# hv_io_gpio.net
KiCad netlist of a schematic drawn in Altium Designer
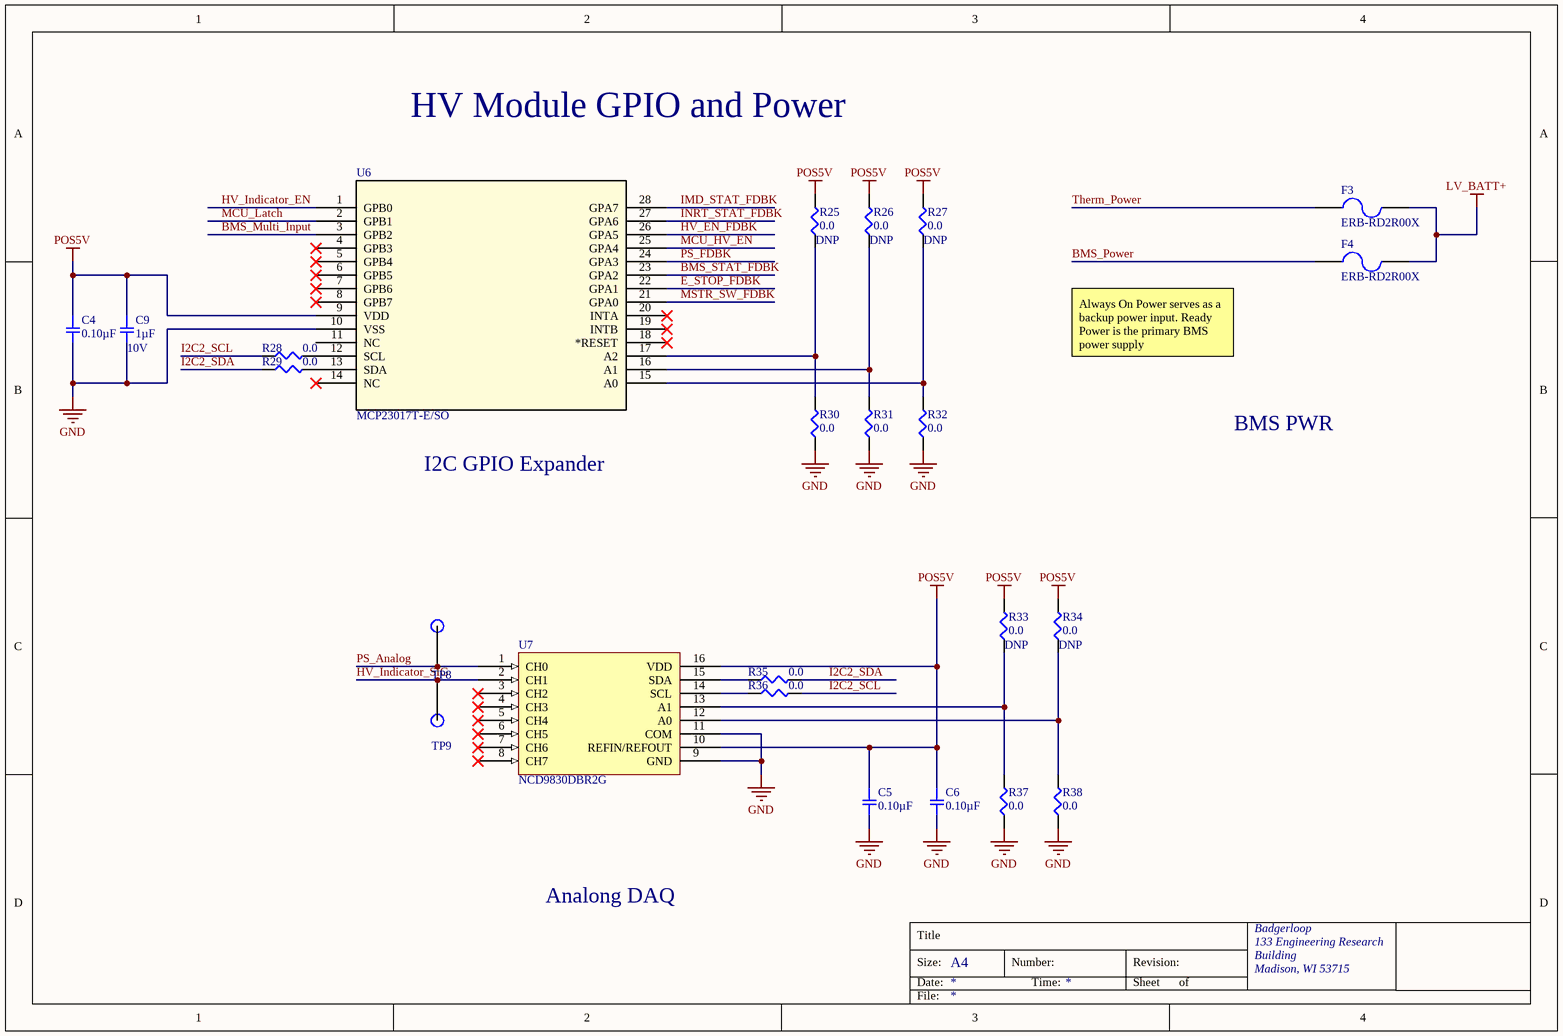
[diagram p0: hv_io_gpio.SchDoc]

(export (version "E")
  (design (tool "Eeschema 10.0.6"))
  (components
    (comp (ref "C4")
      (value "0.10µF")
      (footprint "SMD-0805C")
      (description "CAP CER 0.1UF 50V X7R 0805")
      (fields
        (field (name "DIGI-KEY PART NUMBER") "490-5803-1-ND")
        (field (name "PART NUMBER") "GCJ21BR71H104KA01L")
      )
      (libsource (lib "capacitor") (part "GCJ21BR71H104KA01L"))
    )
    (comp (ref "C5")
      (value "0.10µF")
      (footprint "SMD-0805C")
      (description "CAP CER 0.1UF 50V X7R 0805")
      (fields
        (field (name "DIGI-KEY PART NUMBER") "490-5803-1-ND")
        (field (name "PART NUMBER") "GCJ21BR71H104KA01L")
      )
      (libsource (lib "capacitor") (part "GCJ21BR71H104KA01L"))
    )
    (comp (ref "C6")
      (value "0.10µF")
      (footprint "SMD-0805C")
      (description "CAP CER 0.1UF 50V X7R 0805")
      (fields
        (field (name "DIGI-KEY PART NUMBER") "490-5803-1-ND")
        (field (name "PART NUMBER") "GCJ21BR71H104KA01L")
      )
      (libsource (lib "capacitor") (part "GCJ21BR71H104KA01L"))
    )
    (comp (ref "C9")
      (value "1µF")
      (footprint "SMD-0402C")
      (description "CAP CER 1UF 10V X7S 0402")
      (fields
        (field (name "PART NUMBER") "GCM155C71A105KE38D")
        (field (name "MANUFACTURER") "Murata Electronics North America")
        (field (name "VOLTAGE") "10V")
      )
      (libsource (lib "altium-import") (part "root_0_GCM155C71A105KE38D_"))
    )
    (comp (ref "F3")
      (value "ERB-RD2R00X")
      (footprint "SMD-0402-RES")
      (description "FUSE BOARD MOUNT 2A 32VDC 0402")
      (fields (field (name "MANUFACTURER") "Panasonic"))
      (libsource (lib "temp") (part "ERB-RD2R00X"))
    )
    (comp (ref "F4")
      (value "ERB-RD2R00X")
      (footprint "SMD-0402-RES")
      (description "FUSE BOARD MOUNT 2A 32VDC 0402")
      (fields (field (name "MANUFACTURER") "Panasonic"))
      (libsource (lib "temp") (part "ERB-RD2R00X"))
    )
    (comp (ref "R25")
      (value "0.0")
      (footprint "SMD-0402-RES")
      (description "RES SMD 0.0OHM JUMPER 1/10W 0402")
      (fields
        (field (name "PART NUMBER") "ERJ-2GE0R00X")
        (field (name "DIGI-KEY PART NUMBER") "P0.0JCT-ND")
        (field (name "DNP") "DNP")
      )
      (libsource (lib "altium-import") (part "root_1_ERJ-2GE0R00X_"))
    )
    (comp (ref "R26")
      (value "0.0")
      (footprint "SMD-0402-RES")
      (description "RES SMD 0.0OHM JUMPER 1/10W 0402")
      (fields
        (field (name "PART NUMBER") "ERJ-2GE0R00X")
        (field (name "DIGI-KEY PART NUMBER") "P0.0JCT-ND")
        (field (name "DNP") "DNP")
      )
      (libsource (lib "altium-import") (part "root_1_ERJ-2GE0R00X_"))
    )
    (comp (ref "R27")
      (value "0.0")
      (footprint "SMD-0402-RES")
      (description "RES SMD 0.0OHM JUMPER 1/10W 0402")
      (fields
        (field (name "PART NUMBER") "ERJ-2GE0R00X")
        (field (name "DIGI-KEY PART NUMBER") "P0.0JCT-ND")
        (field (name "DNP") "DNP")
      )
      (libsource (lib "altium-import") (part "root_1_ERJ-2GE0R00X_"))
    )
    (comp (ref "R28")
      (value "0.0")
      (footprint "SMD-0402-RES")
      (description "RES SMD 0.0OHM JUMPER 1/10W 0402")
      (fields (field (name "PART NUMBER") "ERJ-2GE0R00X") (field (name "DIGI-KEY PART NUMBER") "P0.0JCT-ND"))
      (libsource (lib "altium-import") (part "root_0_ERJ-2GE0R00X_"))
    )
    (comp (ref "R29")
      (value "0.0")
      (footprint "SMD-0402-RES")
      (description "RES SMD 0.0OHM JUMPER 1/10W 0402")
      (fields (field (name "PART NUMBER") "ERJ-2GE0R00X") (field (name "DIGI-KEY PART NUMBER") "P0.0JCT-ND"))
      (libsource (lib "altium-import") (part "root_0_ERJ-2GE0R00X_"))
    )
    (comp (ref "R30")
      (value "0.0")
      (footprint "SMD-0402-RES")
      (description "RES SMD 0.0OHM JUMPER 1/10W 0402")
      (fields (field (name "PART NUMBER") "ERJ-2GE0R00X") (field (name "DIGI-KEY PART NUMBER") "P0.0JCT-ND"))
      (libsource (lib "altium-import") (part "root_1_ERJ-2GE0R00X_"))
    )
    (comp (ref "R31")
      (value "0.0")
      (footprint "SMD-0402-RES")
      (description "RES SMD 0.0OHM JUMPER 1/10W 0402")
      (fields (field (name "PART NUMBER") "ERJ-2GE0R00X") (field (name "DIGI-KEY PART NUMBER") "P0.0JCT-ND"))
      (libsource (lib "altium-import") (part "root_1_ERJ-2GE0R00X_"))
    )
    (comp (ref "R32")
      (value "0.0")
      (footprint "SMD-0402-RES")
      (description "RES SMD 0.0OHM JUMPER 1/10W 0402")
      (fields (field (name "PART NUMBER") "ERJ-2GE0R00X") (field (name "DIGI-KEY PART NUMBER") "P0.0JCT-ND"))
      (libsource (lib "altium-import") (part "root_1_ERJ-2GE0R00X_"))
    )
    (comp (ref "R33")
      (value "0.0")
      (footprint "SMD-0402-RES")
      (description "RES SMD 0.0OHM JUMPER 1/10W 0402")
      (fields
        (field (name "PART NUMBER") "ERJ-2GE0R00X")
        (field (name "DIGI-KEY PART NUMBER") "P0.0JCT-ND")
        (field (name "DNP") "DNP")
      )
      (libsource (lib "altium-import") (part "root_1_ERJ-2GE0R00X_"))
    )
    (comp (ref "R34")
      (value "0.0")
      (footprint "SMD-0402-RES")
      (description "RES SMD 0.0OHM JUMPER 1/10W 0402")
      (fields
        (field (name "PART NUMBER") "ERJ-2GE0R00X")
        (field (name "DIGI-KEY PART NUMBER") "P0.0JCT-ND")
        (field (name "DNP") "DNP")
      )
      (libsource (lib "altium-import") (part "root_1_ERJ-2GE0R00X_"))
    )
    (comp (ref "R35")
      (value "0.0")
      (footprint "SMD-0402-RES")
      (description "RES SMD 0.0OHM JUMPER 1/10W 0402")
      (fields (field (name "PART NUMBER") "ERJ-2GE0R00X") (field (name "DIGI-KEY PART NUMBER") "P0.0JCT-ND"))
      (libsource (lib "altium-import") (part "root_0_ERJ-2GE0R00X_"))
    )
    (comp (ref "R36")
      (value "0.0")
      (footprint "SMD-0402-RES")
      (description "RES SMD 0.0OHM JUMPER 1/10W 0402")
      (fields (field (name "PART NUMBER") "ERJ-2GE0R00X") (field (name "DIGI-KEY PART NUMBER") "P0.0JCT-ND"))
      (libsource (lib "altium-import") (part "root_0_ERJ-2GE0R00X_"))
    )
    (comp (ref "R37")
      (value "0.0")
      (footprint "SMD-0402-RES")
      (description "RES SMD 0.0OHM JUMPER 1/10W 0402")
      (fields (field (name "PART NUMBER") "ERJ-2GE0R00X") (field (name "DIGI-KEY PART NUMBER") "P0.0JCT-ND"))
      (libsource (lib "altium-import") (part "root_1_ERJ-2GE0R00X_"))
    )
    (comp (ref "R38")
      (value "0.0")
      (footprint "SMD-0402-RES")
      (description "RES SMD 0.0OHM JUMPER 1/10W 0402")
      (fields (field (name "PART NUMBER") "ERJ-2GE0R00X") (field (name "DIGI-KEY PART NUMBER") "P0.0JCT-ND"))
      (libsource (lib "altium-import") (part "root_1_ERJ-2GE0R00X_"))
    )
    (comp (ref "TP8") (value "TP") (footprint "Test Point") (libsource (lib "misc") (part "TP")))
    (comp (ref "TP9") (value "TP") (footprint "Test Point") (libsource (lib "misc") (part "TP")))
    (comp (ref "U6")
      (value "MCP23017T-E/SO")
      (footprint "SOIC28-W_MC-M")
      (description "IC I/O EXPANDER I2C 16B 28SOIC")
      (fields (field (name "MANUFACTURER") "Microchip"))
      (libsource (lib "ic") (part "MCP23017T-E/SO"))
    )
    (comp (ref "U7")
      (value "NCD9830DBR2G")
      (footprint "TSOP65P640X120_HS-17N")
      (description "IC ADC 8BIT 8CH I2C 16TSSOP")
      (fields (field (name "MANUFACTURER") "ON Semiconductor"))
      (libsource (lib "ic") (part "NCD9830DBR2G"))
    )
  )
  (nets
    (net (code "1") (name "/BMS_Multi_Input") (class "Default")
      (node (ref "U6") (pin "3") (pinfunction "GPB2_3") (pintype "passive"))
    )
    (net (code "2") (name "/BMS_Power") (class "Default")
      (node (ref "F4") (pin "1") (pinfunction "1_1") (pintype "passive"))
    )
    (net (code "3") (name "/BMS_STAT_FDBK") (class "Default")
      (node (ref "U6") (pin "23") (pinfunction "GPA2_23") (pintype "passive"))
    )
    (net (code "4") (name "/E_STOP_FDBK") (class "Default")
      (node (ref "U6") (pin "22") (pinfunction "GPA1_22") (pintype "passive"))
    )
    (net (code "5") (name "/HV_EN_FDBK") (class "Default")
      (node (ref "U6") (pin "26") (pinfunction "GPA5_26") (pintype "passive"))
    )
    (net (code "6") (name "/HV_Indicator_EN") (class "Default")
      (node (ref "U6") (pin "1") (pinfunction "GPB0_1") (pintype "passive"))
    )
    (net (code "7") (name "/HV_Indicator_SIG") (class "Default")
      (node (ref "TP9") (pin "1") (pinfunction "1_1") (pintype "passive"))
      (node (ref "U7") (pin "2") (pinfunction "CH1_2") (pintype "input"))
    )
    (net (code "8") (name "/I2C2_SCL") (class "Default")
      (node (ref "R28") (pin "1") (pinfunction "1_1") (pintype "passive"))
      (node (ref "R36") (pin "2") (pinfunction "2_2") (pintype "passive"))
    )
    (net (code "9") (name "/I2C2_SDA") (class "Default")
      (node (ref "R29") (pin "1") (pinfunction "1_1") (pintype "passive"))
      (node (ref "R35") (pin "2") (pinfunction "2_2") (pintype "passive"))
    )
    (net (code "10") (name "/IMD_STAT_FDBK") (class "Default")
      (node (ref "U6") (pin "28") (pinfunction "GPA7_28") (pintype "passive"))
    )
    (net (code "11") (name "/INRT_STAT_FDBK") (class "Default")
      (node (ref "U6") (pin "27") (pinfunction "GPA6_27") (pintype "passive"))
    )
    (net (code "12") (name "/MCU_HV_EN") (class "Default")
      (node (ref "U6") (pin "25") (pinfunction "GPA4_25") (pintype "passive"))
    )
    (net (code "13") (name "/MCU_Latch") (class "Default")
      (node (ref "U6") (pin "2") (pinfunction "GPB1_2") (pintype "passive"))
    )
    (net (code "14") (name "/MSTR_SW_FDBK") (class "Default")
      (node (ref "U6") (pin "21") (pinfunction "GPA0_21") (pintype "passive"))
    )
    (net (code "15") (name "/PS_Analog") (class "Default")
      (node (ref "TP8") (pin "1") (pinfunction "1_1") (pintype "passive"))
      (node (ref "U7") (pin "1") (pinfunction "CH0_1") (pintype "input"))
    )
    (net (code "16") (name "/PS_FDBK") (class "Default")
      (node (ref "U6") (pin "24") (pinfunction "GPA3_24") (pintype "passive"))
    )
    (net (code "17") (name "/Therm_Power") (class "Default")
      (node (ref "F3") (pin "1") (pinfunction "1_1") (pintype "passive"))
    )
    (net (code "18") (name "GND") (class "Default")
      (node (ref "C4") (pin "2") (pinfunction "2_2") (pintype "passive"))
      (node (ref "C5") (pin "2") (pinfunction "2_2") (pintype "passive"))
      (node (ref "C6") (pin "2") (pinfunction "2_2") (pintype "passive"))
      (node (ref "C9") (pin "2") (pinfunction "2_2") (pintype "passive"))
      (node (ref "R30") (pin "1") (pinfunction "1_1") (pintype "passive"))
      (node (ref "R31") (pin "1") (pinfunction "1_1") (pintype "passive"))
      (node (ref "R32") (pin "1") (pinfunction "1_1") (pintype "passive"))
      (node (ref "R37") (pin "1") (pinfunction "1_1") (pintype "passive"))
      (node (ref "R38") (pin "1") (pinfunction "1_1") (pintype "passive"))
      (node (ref "U6") (pin "10") (pinfunction "VSS_10") (pintype "passive"))
      (node (ref "U7") (pin "11") (pinfunction "COM_11") (pintype "power_in"))
      (node (ref "U7") (pin "9") (pinfunction "GND_9") (pintype "power_in"))
    )
    (net (code "19") (name "LV_BATT+") (class "Default")
      (node (ref "F3") (pin "2") (pinfunction "2_2") (pintype "passive"))
      (node (ref "F4") (pin "2") (pinfunction "2_2") (pintype "passive"))
    )
    (net (code "20") (name "Net-(U6-A0)") (class "Default")
      (node (ref "R27") (pin "1") (pinfunction "1_1") (pintype "passive"))
      (node (ref "R32") (pin "2") (pinfunction "2_2") (pintype "passive"))
      (node (ref "U6") (pin "15") (pinfunction "A0_15") (pintype "passive"))
    )
    (net (code "21") (name "Net-(U6-A1)") (class "Default")
      (node (ref "R26") (pin "1") (pinfunction "1_1") (pintype "passive"))
      (node (ref "R31") (pin "2") (pinfunction "2_2") (pintype "passive"))
      (node (ref "U6") (pin "16") (pinfunction "A1_16") (pintype "passive"))
    )
    (net (code "22") (name "Net-(U6-A2)") (class "Default")
      (node (ref "R25") (pin "1") (pinfunction "1_1") (pintype "passive"))
      (node (ref "R30") (pin "2") (pinfunction "2_2") (pintype "passive"))
      (node (ref "U6") (pin "17") (pinfunction "A2_17") (pintype "passive"))
    )
    (net (code "23") (name "Net-(U6-SCL)") (class "Default")
      (node (ref "R28") (pin "2") (pinfunction "2_2") (pintype "passive"))
      (node (ref "U6") (pin "12") (pinfunction "SCL_12") (pintype "passive"))
    )
    (net (code "24") (name "Net-(U6-SDA)") (class "Default")
      (node (ref "R29") (pin "2") (pinfunction "2_2") (pintype "passive"))
      (node (ref "U6") (pin "13") (pinfunction "SDA_13") (pintype "passive"))
    )
    (net (code "25") (name "Net-(U7-A0)") (class "Default")
      (node (ref "R34") (pin "1") (pinfunction "1_1") (pintype "passive"))
      (node (ref "R38") (pin "2") (pinfunction "2_2") (pintype "passive"))
      (node (ref "U7") (pin "12") (pinfunction "A0_12") (pintype "passive"))
    )
    (net (code "26") (name "Net-(U7-A1)") (class "Default")
      (node (ref "R33") (pin "1") (pinfunction "1_1") (pintype "passive"))
      (node (ref "R37") (pin "2") (pinfunction "2_2") (pintype "passive"))
      (node (ref "U7") (pin "13") (pinfunction "A1_13") (pintype "passive"))
    )
    (net (code "27") (name "Net-(U7-SCL)") (class "Default")
      (node (ref "R36") (pin "1") (pinfunction "1_1") (pintype "passive"))
      (node (ref "U7") (pin "14") (pinfunction "SCL_14") (pintype "passive"))
    )
    (net (code "28") (name "Net-(U7-SDA)") (class "Default")
      (node (ref "R35") (pin "1") (pinfunction "1_1") (pintype "passive"))
      (node (ref "U7") (pin "15") (pinfunction "SDA_15") (pintype "passive"))
    )
    (net (code "29") (name "POS5V") (class "Default")
      (node (ref "C4") (pin "1") (pinfunction "1_1") (pintype "passive"))
      (node (ref "C5") (pin "1") (pinfunction "1_1") (pintype "passive"))
      (node (ref "C6") (pin "1") (pinfunction "1_1") (pintype "passive"))
      (node (ref "C9") (pin "1") (pinfunction "1_1") (pintype "passive"))
      (node (ref "R25") (pin "2") (pinfunction "2_2") (pintype "passive"))
      (node (ref "R26") (pin "2") (pinfunction "2_2") (pintype "passive"))
      (node (ref "R27") (pin "2") (pinfunction "2_2") (pintype "passive"))
      (node (ref "R33") (pin "2") (pinfunction "2_2") (pintype "passive"))
      (node (ref "R34") (pin "2") (pinfunction "2_2") (pintype "passive"))
      (node (ref "U6") (pin "9") (pinfunction "VDD_9") (pintype "passive"))
      (node (ref "U7") (pin "10") (pinfunction "REFIN/REFOUT_10") (pintype "power_in"))
      (node (ref "U7") (pin "16") (pinfunction "VDD_16") (pintype "power_in"))
    )
    (net (code "30") (name "unconnected-(U6-*RESET-Pad18)") (class "Default")
      (node (ref "U6") (pin "18") (pinfunction "*RESET_18") (pintype "passive+no_connect"))
    )
    (net (code "31") (name "unconnected-(U6-GPB3-Pad4)") (class "Default")
      (node (ref "U6") (pin "4") (pinfunction "GPB3_4") (pintype "passive+no_connect"))
    )
    (net (code "32") (name "unconnected-(U6-GPB4-Pad5)") (class "Default")
      (node (ref "U6") (pin "5") (pinfunction "GPB4_5") (pintype "passive+no_connect"))
    )
    (net (code "33") (name "unconnected-(U6-GPB5-Pad6)") (class "Default")
      (node (ref "U6") (pin "6") (pinfunction "GPB5_6") (pintype "passive+no_connect"))
    )
    (net (code "34") (name "unconnected-(U6-GPB6-Pad7)") (class "Default")
      (node (ref "U6") (pin "7") (pinfunction "GPB6_7") (pintype "passive+no_connect"))
    )
    (net (code "35") (name "unconnected-(U6-GPB7-Pad8)") (class "Default")
      (node (ref "U6") (pin "8") (pinfunction "GPB7_8") (pintype "passive+no_connect"))
    )
    (net (code "36") (name "unconnected-(U6-INTA-Pad20)") (class "Default")
      (node (ref "U6") (pin "20") (pinfunction "INTA_20") (pintype "passive+no_connect"))
    )
    (net (code "37") (name "unconnected-(U6-INTB-Pad19)") (class "Default")
      (node (ref "U6") (pin "19") (pinfunction "INTB_19") (pintype "passive+no_connect"))
    )
    (net (code "38") (name "unconnected-(U6-NC-Pad11)") (class "Default")
      (node (ref "U6") (pin "11") (pinfunction "NC_11") (pintype "passive"))
    )
    (net (code "39") (name "unconnected-(U6-NC-Pad14)") (class "Default")
      (node (ref "U6") (pin "14") (pinfunction "NC_14") (pintype "passive+no_connect"))
    )
    (net (code "40") (name "unconnected-(U7-CH2-Pad3)") (class "Default")
      (node (ref "U7") (pin "3") (pinfunction "CH2_3") (pintype "input+no_connect"))
    )
    (net (code "41") (name "unconnected-(U7-CH3-Pad4)") (class "Default")
      (node (ref "U7") (pin "4") (pinfunction "CH3_4") (pintype "input+no_connect"))
    )
    (net (code "42") (name "unconnected-(U7-CH4-Pad5)") (class "Default")
      (node (ref "U7") (pin "5") (pinfunction "CH4_5") (pintype "input+no_connect"))
    )
    (net (code "43") (name "unconnected-(U7-CH5-Pad6)") (class "Default")
      (node (ref "U7") (pin "6") (pinfunction "CH5_6") (pintype "input+no_connect"))
    )
    (net (code "44") (name "unconnected-(U7-CH6-Pad7)") (class "Default")
      (node (ref "U7") (pin "7") (pinfunction "CH6_7") (pintype "input+no_connect"))
    )
    (net (code "45") (name "unconnected-(U7-CH7-Pad8)") (class "Default")
      (node (ref "U7") (pin "8") (pinfunction "CH7_8") (pintype "input+no_connect"))
    )
  )
)
